# CurrentSenseAmpBias.net
KiCad netlist of a schematic drawn in Altium Designer
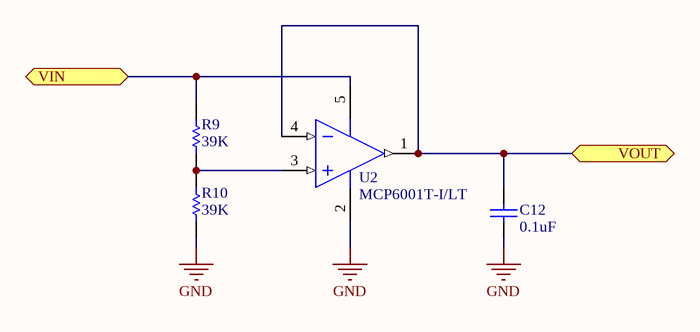
[diagram p0: CurrentSenseAmpBias.SchDoc]

(export (version "E")
  (design (tool "Eeschema 10.0.6"))
  (components
    (comp (ref "C12")
      (value "0.1uF")
      (footprint "CAPC0603(1608)100_L")
      (description "CAP 100nF 100V ±10% 0603 (1608 Metric) Thickness 1mm SMD")
      (fields (field (name "TOLERANCE") "Â±10%"))
      (libsource (lib "Altium Content Vault") (part "CAP"))
    )
    (comp (ref "R9")
      (value "39K")
      (footprint "RESC0603(1608)_L")
      (description "39K 0.1W 1% 0603 (1608 Metric)  SMD")
      (fields (field (name "TOLERANCE") "1 %") (field (name "POWER") "0.1 W"))
      (libsource (lib "Altium Content Vault") (part "CMP-1012-00689-1"))
    )
    (comp (ref "R10")
      (value "39K")
      (footprint "RESC0603(1608)_L")
      (description "39K 0.1W 1% 0603 (1608 Metric)  SMD")
      (fields (field (name "TOLERANCE") "1 %") (field (name "POWER") "0.1 W"))
      (libsource (lib "Altium Content Vault") (part "CMP-1012-00689-1"))
    )
    (comp (ref "U2")
      (value "MCP6001T-I/LT")
      (footprint "SC70-LT5_M")
      (description "1 MHz, Low-Power Operational Amplifier, 5-Pin SC-70, Industrial Temperature, Tape and Reel")
      (libsource (lib "Altium Content Vault") (part "AMP-OPA-MCP6001-SOT5"))
    )
  )
  (nets
    (net (code "1") (name "/VIN") (class "Default")
      (node (ref "R9") (pin "2") (pinfunction "2_2") (pintype "passive"))
      (node (ref "U2") (pin "5") (pinfunction "VDD_5") (pintype "power_in"))
    )
    (net (code "2") (name "/VOUT") (class "Default")
      (node (ref "C12") (pin "2") (pinfunction "2_2") (pintype "passive"))
      (node (ref "U2") (pin "1") (pinfunction "VOUT_1") (pintype "output"))
      (node (ref "U2") (pin "4") (pinfunction "VIN-_4") (pintype "input"))
    )
    (net (code "3") (name "GND") (class "Default")
      (node (ref "C12") (pin "1") (pinfunction "1_1") (pintype "passive"))
      (node (ref "R10") (pin "1") (pinfunction "1_1") (pintype "passive"))
      (node (ref "U2") (pin "2") (pinfunction "VSS_2") (pintype "power_in"))
    )
    (net (code "4") (name "Net-(U2-VIN+)") (class "Default")
      (node (ref "R10") (pin "2") (pinfunction "2_2") (pintype "passive"))
      (node (ref "R9") (pin "1") (pinfunction "1_1") (pintype "passive"))
      (node (ref "U2") (pin "3") (pinfunction "VIN+_3") (pintype "input"))
    )
  )
)
